# hbridgeC.net
KiCad netlist of a schematic drawn in Altium Designer
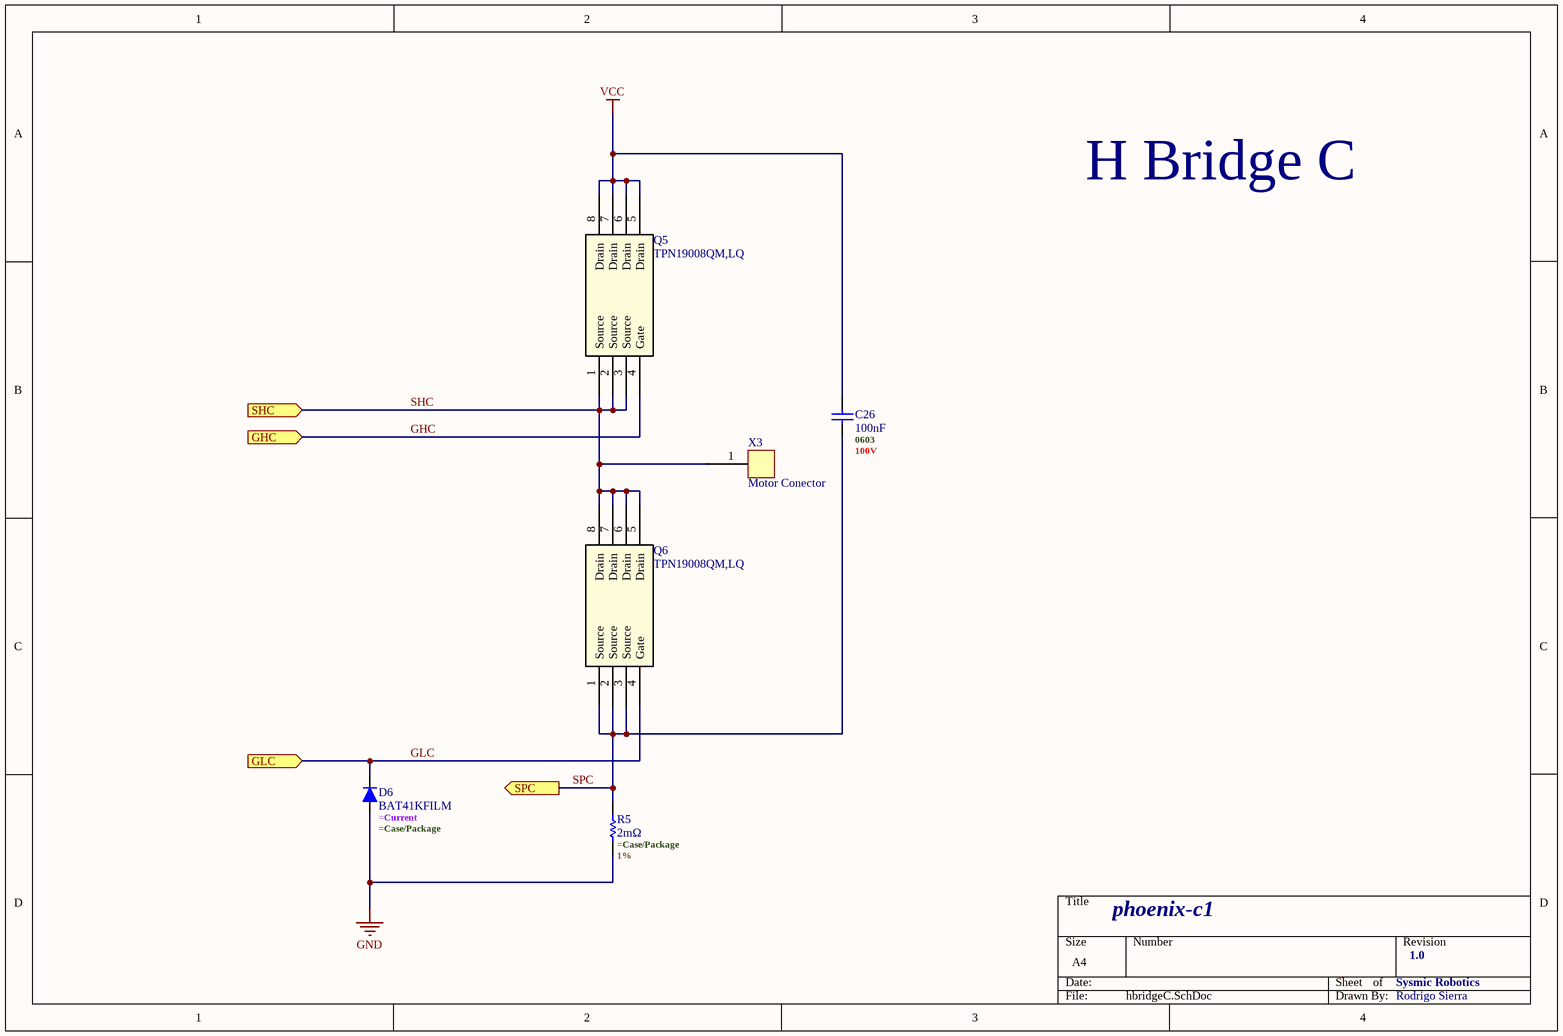
[diagram p0: hbridgeC.SchDoc]

(export (version "E")
  (design (tool "Eeschema 10.0.6"))
  (components
    (comp (ref "C26")
      (value "100nF")
      (footprint "C0603 - MURATA")
      (description "Cap Ceramic 0.1uF 100V X7R 10% Pad SMD 0603 Soft Termination 125C Automotive T/R")
      (fields
        (field (name "MANUFACTURER") "Murata")
        (field (name "MANUFACTURER PART NUMBER") "GCJ188R72A104KA01D")
        (field (name ".CASE/PACKAGE") "0603")
        (field (name ".VOLTAGE RATING (DC)") "100V")
      )
      (libsource (lib "CAP - GCJ188R72A104KA01D") (part "GCJ188R72A104KA01D"))
    )
    (comp (ref "D6")
      (value "BAT41KFILM")
      (footprint "DSOD-523 - STMicroelectronics")
      (description "Low Capacitance Small Signal 200 mA 1 V Schottky Diode Surface Mount - SOD-523")
      (fields (field (name "MANUFACTURER") "STMicroelectronics"))
      (libsource (lib "DIODE - BAT41KFILM") (part "BAT41KFILM"))
    )
    (comp (ref "Q5")
      (value "TPN19008QM,LQ")
      (footprint "8-TSON - TOSHIBA")
      (description "Power MOSFET, N Channel, 80 V, 38 A, 0.0147 ohm, TSON, Surface Mount")
      (fields (field (name "COPYRIGHT") "Copyright (C) 2025 Ultra Librarian. All rights reserved."))
      (libsource (lib "MOSFET - TPN19008QM_LQ") (part "TPN19008QM,LQ"))
    )
    (comp (ref "Q6")
      (value "TPN19008QM,LQ")
      (footprint "8-TSON - TOSHIBA")
      (description "Power MOSFET, N Channel, 80 V, 38 A, 0.0147 ohm, TSON, Surface Mount")
      (fields (field (name "COPYRIGHT") "Copyright (C) 2025 Ultra Librarian. All rights reserved."))
      (libsource (lib "MOSFET - TPN19008QM_LQ") (part "TPN19008QM,LQ"))
    )
    (comp (ref "R5")
      (value "2mΩ")
      (footprint "R0805 - SEI")
      (description "Res Metal Alloy 0805 0.002 Ohm 1% 1W ±75ppm/C Pad SMD T/R Automotive AEC-Q200")
      (fields
        (field (name "MANUFACTURER") "Stackpole Electronics")
        (field (name "MANUFACTURER PART NUMBER") "CSSH0805FT2L00")
        (field (name ".TOLERANCE") "1%")
      )
      (libsource (lib "RES - CSSH0805FT2L00") (part "CSSH0805FT2L00"))
    )
    (comp (ref "X3")
      (value "Motor Conector")
      (footprint "CONN_PHASE01x01")
      (description "Generic connector, single row")
      (libsource (lib "CONN - MOTOR PHASE") (part "Conn_01x01"))
    )
  )
  (nets
    (net (code "1") (name "/GHC") (class "Default")
      (node (ref "Q5") (pin "4") (pinfunction "Gate_4") (pintype "passive"))
    )
    (net (code "2") (name "/GLC") (class "Default")
      (node (ref "D6") (pin "1") (pinfunction "1_1") (pintype "passive"))
      (node (ref "Q6") (pin "4") (pinfunction "Gate_4") (pintype "passive"))
    )
    (net (code "3") (name "/SHC") (class "Default")
      (node (ref "Q5") (pin "1") (pinfunction "Source_1") (pintype "passive"))
      (node (ref "Q5") (pin "2") (pinfunction "Source_2") (pintype "passive"))
      (node (ref "Q5") (pin "3") (pinfunction "Source_3") (pintype "passive"))
      (node (ref "Q6") (pin "5") (pinfunction "Drain_5") (pintype "passive"))
      (node (ref "Q6") (pin "6") (pinfunction "Drain_6") (pintype "passive"))
      (node (ref "Q6") (pin "7") (pinfunction "Drain_7") (pintype "passive"))
      (node (ref "Q6") (pin "8") (pinfunction "Drain_8") (pintype "passive"))
      (node (ref "X3") (pin "1") (pinfunction "Conn_1") (pintype "passive"))
    )
    (net (code "4") (name "/SPC") (class "Default")
      (node (ref "C26") (pin "1") (pinfunction "1_1") (pintype "passive"))
      (node (ref "Q6") (pin "1") (pinfunction "Source_1") (pintype "passive"))
      (node (ref "Q6") (pin "2") (pinfunction "Source_2") (pintype "passive"))
      (node (ref "Q6") (pin "3") (pinfunction "Source_3") (pintype "passive"))
      (node (ref "R5") (pin "2") (pinfunction "2_2") (pintype "passive"))
    )
    (net (code "5") (name "GND") (class "Default")
      (node (ref "D6") (pin "2") (pinfunction "2_2") (pintype "passive"))
      (node (ref "R5") (pin "1") (pinfunction "1_1") (pintype "passive"))
    )
    (net (code "6") (name "VCC") (class "Default")
      (node (ref "C26") (pin "2") (pinfunction "2_2") (pintype "passive"))
      (node (ref "Q5") (pin "5") (pinfunction "Drain_5") (pintype "passive"))
      (node (ref "Q5") (pin "6") (pinfunction "Drain_6") (pintype "passive"))
      (node (ref "Q5") (pin "7") (pinfunction "Drain_7") (pintype "passive"))
      (node (ref "Q5") (pin "8") (pinfunction "Drain_8") (pintype "passive"))
    )
  )
)
